# gateway_v1_2A.net
KiCad netlist of a schematic drawn in EAGLE
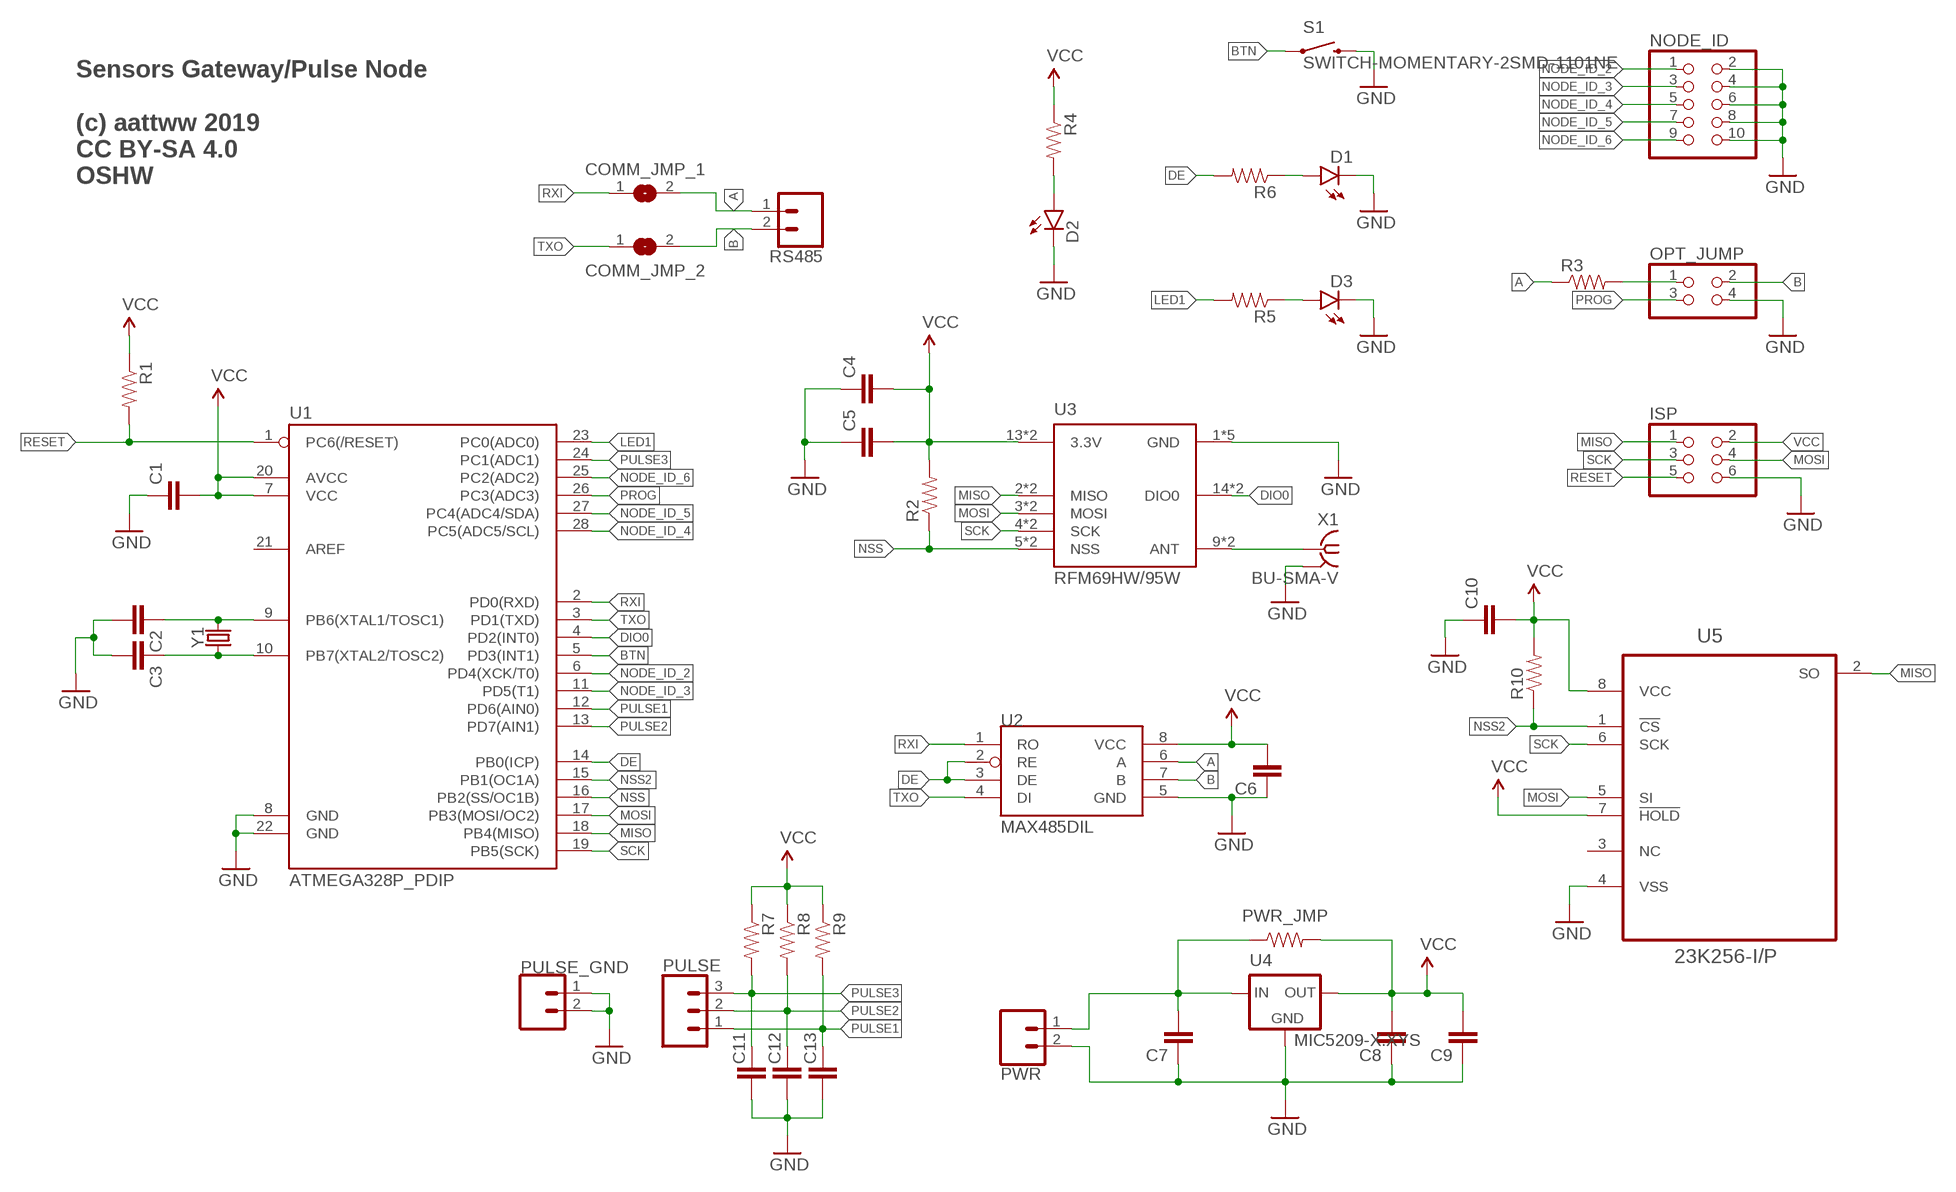
[diagram p0: schematic, sheet 1]

(export (version "E")
  (design (tool "Eeschema 10.0.6"))
  (components
    (comp (ref "C1")
      (value "CAP1206")
      (footprint "eagle-import:1206")
      (libsource (lib "eagle-import") (part "CAP1206"))
    )
    (comp (ref "C2")
      (value "CAP1206")
      (footprint "eagle-import:1206")
      (libsource (lib "eagle-import") (part "CAP1206"))
    )
    (comp (ref "C3")
      (value "CAP1206")
      (footprint "eagle-import:1206")
      (libsource (lib "eagle-import") (part "CAP1206"))
    )
    (comp (ref "C4")
      (value "CAP1206")
      (footprint "eagle-import:1206")
      (libsource (lib "eagle-import") (part "CAP1206"))
    )
    (comp (ref "C5")
      (value "CAP1206")
      (footprint "eagle-import:1206")
      (libsource (lib "eagle-import") (part "CAP1206"))
    )
    (comp (ref "C6")
      (value "CAP1206")
      (footprint "eagle-import:1206")
      (libsource (lib "eagle-import") (part "CAP1206"))
    )
    (comp (ref "C7")
      (value "CAP1206")
      (footprint "eagle-import:1206")
      (libsource (lib "eagle-import") (part "CAP1206"))
    )
    (comp (ref "C8")
      (value "CAP1206")
      (footprint "eagle-import:1206")
      (libsource (lib "eagle-import") (part "CAP1206"))
    )
    (comp (ref "C9")
      (value "CAP1206")
      (footprint "eagle-import:1206")
      (libsource (lib "eagle-import") (part "CAP1206"))
    )
    (comp (ref "C10")
      (value "CAP1206")
      (footprint "eagle-import:1206")
      (libsource (lib "eagle-import") (part "CAP1206"))
    )
    (comp (ref "C11")
      (value "CAP1206")
      (footprint "eagle-import:1206")
      (libsource (lib "eagle-import") (part "CAP1206"))
    )
    (comp (ref "C12")
      (value "CAP1206")
      (footprint "eagle-import:1206")
      (libsource (lib "eagle-import") (part "CAP1206"))
    )
    (comp (ref "C13")
      (value "CAP1206")
      (footprint "eagle-import:1206")
      (libsource (lib "eagle-import") (part "CAP1206"))
    )
    (comp (ref "COMM_JMP_1")
      (value "SJ")
      (footprint "eagle-import:SJ")
      (libsource (lib "eagle-import") (part "SJ"))
    )
    (comp (ref "COMM_JMP_2")
      (value "SJ")
      (footprint "eagle-import:SJ")
      (libsource (lib "eagle-import") (part "SJ"))
    )
    (comp (ref "D1")
      (value "LED1206")
      (footprint "eagle-import:LED-1206")
      (libsource (lib "eagle-import") (part "LED1206"))
    )
    (comp (ref "D2")
      (value "LED1206")
      (footprint "eagle-import:LED-1206")
      (libsource (lib "eagle-import") (part "LED1206"))
    )
    (comp (ref "D3")
      (value "LED1206")
      (footprint "eagle-import:LED-1206")
      (libsource (lib "eagle-import") (part "LED1206"))
    )
    (comp (ref "ISP")
      (value "PINHD-2X3")
      (footprint "eagle-import:2X03")
      (libsource (lib "eagle-import") (part "PINHD-2X3"))
    )
    (comp (ref "NODE_ID")
      (value "PINHD-2X5")
      (footprint "eagle-import:2X05")
      (libsource (lib "eagle-import") (part "PINHD-2X5"))
    )
    (comp (ref "OPT_JUMP")
      (value "PINHD-2X2")
      (footprint "eagle-import:2X02")
      (libsource (lib "eagle-import") (part "PINHD-2X2"))
    )
    (comp (ref "PULSE")
      (value "CONN_03-SCREW-5MM")
      (footprint "eagle-import:SCREWTERMINAL-5MM-3")
      (libsource (lib "eagle-import") (part "CONN_03-SCREW-5MM"))
    )
    (comp (ref "PULSE_GND")
      (value "CONN_025MM")
      (footprint "eagle-import:SCREWTERMINAL-5MM-2")
      (libsource (lib "eagle-import") (part "CONN_025MM"))
    )
    (comp (ref "PWR")
      (value "CONN_025MM")
      (footprint "eagle-import:SCREWTERMINAL-5MM-2")
      (libsource (lib "eagle-import") (part "CONN_025MM"))
    )
    (comp (ref "PWR_JMP")
      (value "RESISTOR1206")
      (footprint "eagle-import:1206")
      (libsource (lib "eagle-import") (part "RESISTOR1206"))
    )
    (comp (ref "R1")
      (value "RESISTOR1206")
      (footprint "eagle-import:1206")
      (libsource (lib "eagle-import") (part "RESISTOR1206"))
    )
    (comp (ref "R2")
      (value "RESISTOR1206")
      (footprint "eagle-import:1206")
      (libsource (lib "eagle-import") (part "RESISTOR1206"))
    )
    (comp (ref "R3")
      (value "RESISTOR1206")
      (footprint "eagle-import:1206")
      (libsource (lib "eagle-import") (part "RESISTOR1206"))
    )
    (comp (ref "R4")
      (value "RESISTOR1206")
      (footprint "eagle-import:1206")
      (libsource (lib "eagle-import") (part "RESISTOR1206"))
    )
    (comp (ref "R5")
      (value "RESISTOR1206")
      (footprint "eagle-import:1206")
      (libsource (lib "eagle-import") (part "RESISTOR1206"))
    )
    (comp (ref "R6")
      (value "RESISTOR1206")
      (footprint "eagle-import:1206")
      (libsource (lib "eagle-import") (part "RESISTOR1206"))
    )
    (comp (ref "R7")
      (value "RESISTOR1206")
      (footprint "eagle-import:1206")
      (libsource (lib "eagle-import") (part "RESISTOR1206"))
    )
    (comp (ref "R8")
      (value "RESISTOR1206")
      (footprint "eagle-import:1206")
      (libsource (lib "eagle-import") (part "RESISTOR1206"))
    )
    (comp (ref "R9")
      (value "RESISTOR1206")
      (footprint "eagle-import:1206")
      (libsource (lib "eagle-import") (part "RESISTOR1206"))
    )
    (comp (ref "R10")
      (value "RESISTOR1206")
      (footprint "eagle-import:1206")
      (libsource (lib "eagle-import") (part "RESISTOR1206"))
    )
    (comp (ref "RS485")
      (value "CONN_025MM")
      (footprint "eagle-import:SCREWTERMINAL-5MM-2")
      (libsource (lib "eagle-import") (part "CONN_025MM"))
    )
    (comp (ref "S1")
      (value "SWITCH-MOMENTARY-2SMD-1101NE")
      (footprint "eagle-import:TACTILE-SWITCH-1101NE")
      (libsource (lib "eagle-import") (part "SWITCH-MOMENTARY-2SMD-1101NE"))
    )
    (comp (ref "U1")
      (value "ATMEGA328P_PDIP")
      (footprint "eagle-import:DIL28-3")
      (libsource (lib "eagle-import") (part "ATMEGA328P_PDIP"))
    )
    (comp (ref "U2")
      (value "MAX485DIL")
      (footprint "eagle-import:DIL08")
      (libsource (lib "eagle-import") (part "MAX485DIL"))
    )
    (comp (ref "U3")
      (value "RFM69HW/95W")
      (footprint "eagle-import:RFM69HW_95W")
      (libsource (lib "eagle-import") (part "RFM69HW/95W"))
    )
    (comp (ref "U4")
      (value "MIC5209-X.XYS")
      (footprint "eagle-import:SOT223")
      (libsource (lib "eagle-import") (part "MIC5209-X.XYS"))
    )
    (comp (ref "U5")
      (value "23K256-I/P")
      (footprint "eagle-import:DIP254P762X533-8")
      (fields (field (name "MPN") "23K256-I/P "))
      (libsource (lib "eagle-import") (part "23K256-I/P"))
    )
    (comp (ref "X1")
      (value "BU-SMA-V")
      (footprint "eagle-import:BU-SMA-V")
      (libsource (lib "eagle-import") (part "BU-SMA-V"))
    )
    (comp (ref "Y1")
      (value "CRYSTALPTH-HC49US")
      (footprint "eagle-import:HC49US")
      (libsource (lib "eagle-import") (part "CRYSTALPTH-HC49US"))
    )
  )
  (nets
    (net (code "1") (name "A") (class "Default")
      (node (ref "COMM_JMP_1") (pin "2") (pinfunction "2_2") (pintype "passive"))
      (node (ref "R3") (pin "1") (pinfunction "1_1") (pintype "passive"))
      (node (ref "RS485") (pin "1") (pinfunction "1_1") (pintype "passive"))
      (node (ref "U2") (pin "6") (pinfunction "A_6") (pintype "bidirectional"))
    )
    (net (code "2") (name "B") (class "Default")
      (node (ref "COMM_JMP_2") (pin "2") (pinfunction "2_2") (pintype "passive"))
      (node (ref "OPT_JUMP") (pin "2") (pinfunction "2_2") (pintype "passive"))
      (node (ref "RS485") (pin "2") (pinfunction "2_2") (pintype "passive"))
      (node (ref "U2") (pin "7") (pinfunction "B_7") (pintype "bidirectional"))
    )
    (net (code "3") (name "BTN") (class "Default")
      (node (ref "S1") (pin "1") (pinfunction "1_1") (pintype "passive"))
      (node (ref "U1") (pin "5") (pinfunction "PD3(INT1)_5") (pintype "bidirectional"))
    )
    (net (code "4") (name "DE") (class "Default")
      (node (ref "R6") (pin "2") (pinfunction "2_2") (pintype "passive"))
      (node (ref "U1") (pin "14") (pinfunction "PB0(ICP)_14") (pintype "bidirectional"))
      (node (ref "U2") (pin "2") (pinfunction "RE_2") (pintype "bidirectional"))
      (node (ref "U2") (pin "3") (pinfunction "DE_3") (pintype "bidirectional"))
    )
    (net (code "5") (name "DIO0") (class "Default")
      (node (ref "U1") (pin "4") (pinfunction "PD2(INT0)_4") (pintype "bidirectional"))
      (node (ref "U3") (pin "14") (pinfunction "DIO0_14") (pintype "bidirectional"))
      (node (ref "U3") (pin "22") (pinfunction "DIO0_22") (pintype "bidirectional"))
    )
    (net (code "6") (name "GND") (class "Default")
      (node (ref "C1") (pin "1") (pinfunction "1_1") (pintype "passive"))
      (node (ref "C10") (pin "1") (pinfunction "1_1") (pintype "passive"))
      (node (ref "C11") (pin "2") (pinfunction "2_2") (pintype "passive"))
      (node (ref "C12") (pin "2") (pinfunction "2_2") (pintype "passive"))
      (node (ref "C13") (pin "2") (pinfunction "2_2") (pintype "passive"))
      (node (ref "C2") (pin "2") (pinfunction "2_2") (pintype "passive"))
      (node (ref "C3") (pin "2") (pinfunction "2_2") (pintype "passive"))
      (node (ref "C4") (pin "1") (pinfunction "1_1") (pintype "passive"))
      (node (ref "C5") (pin "1") (pinfunction "1_1") (pintype "passive"))
      (node (ref "C6") (pin "1") (pinfunction "1_1") (pintype "passive"))
      (node (ref "C7") (pin "1") (pinfunction "1_1") (pintype "passive"))
      (node (ref "C8") (pin "1") (pinfunction "1_1") (pintype "passive"))
      (node (ref "C9") (pin "1") (pinfunction "1_1") (pintype "passive"))
      (node (ref "D1") (pin "C") (pinfunction "C_C") (pintype "passive"))
      (node (ref "D2") (pin "C") (pinfunction "C_C") (pintype "passive"))
      (node (ref "D3") (pin "C") (pinfunction "C_C") (pintype "passive"))
      (node (ref "ISP") (pin "6") (pinfunction "6_6") (pintype "passive"))
      (node (ref "NODE_ID") (pin "10") (pinfunction "10_10") (pintype "passive"))
      (node (ref "NODE_ID") (pin "2") (pinfunction "2_2") (pintype "passive"))
      (node (ref "NODE_ID") (pin "4") (pinfunction "4_4") (pintype "passive"))
      (node (ref "NODE_ID") (pin "6") (pinfunction "6_6") (pintype "passive"))
      (node (ref "NODE_ID") (pin "8") (pinfunction "8_8") (pintype "passive"))
      (node (ref "OPT_JUMP") (pin "4") (pinfunction "4_4") (pintype "passive"))
      (node (ref "PULSE_GND") (pin "1") (pinfunction "1_1") (pintype "passive"))
      (node (ref "PULSE_GND") (pin "2") (pinfunction "2_2") (pintype "passive"))
      (node (ref "PWR") (pin "2") (pinfunction "2_2") (pintype "passive"))
      (node (ref "S1") (pin "2") (pinfunction "2_2") (pintype "passive"))
      (node (ref "U1") (pin "22") (pinfunction "GND_22") (pintype "bidirectional"))
      (node (ref "U1") (pin "8") (pinfunction "GND_8") (pintype "bidirectional"))
      (node (ref "U2") (pin "5") (pinfunction "GND_5") (pintype "bidirectional"))
      (node (ref "U3") (pin "1") (pinfunction "GND_1") (pintype "power_in"))
      (node (ref "U3") (pin "10") (pinfunction "GND_10") (pintype "power_in"))
      (node (ref "U3") (pin "29") (pinfunction "GND_29") (pintype "power_in"))
      (node (ref "U3") (pin "31") (pinfunction "GND_31") (pintype "power_in"))
      (node (ref "U3") (pin "8") (pinfunction "GND_8") (pintype "power_in"))
      (node (ref "U4") (pin "2") (pinfunction "GND_2") (pintype "passive"))
      (node (ref "U4") (pin "4") (pinfunction "GND_4") (pintype "passive"))
      (node (ref "U5") (pin "4") (pinfunction "VSS_4") (pintype "passive"))
      (node (ref "X1") (pin "2") (pinfunction "2_2") (pintype "passive"))
      (node (ref "X1") (pin "3") (pinfunction "2_3") (pintype "passive"))
      (node (ref "X1") (pin "4") (pinfunction "2_4") (pintype "passive"))
      (node (ref "X1") (pin "5") (pinfunction "2_5") (pintype "passive"))
    )
    (net (code "7") (name "LED1") (class "Default")
      (node (ref "R5") (pin "2") (pinfunction "2_2") (pintype "passive"))
      (node (ref "U1") (pin "23") (pinfunction "PC0(ADC0)_23") (pintype "bidirectional"))
    )
    (net (code "8") (name "MISO") (class "Default")
      (node (ref "ISP") (pin "1") (pinfunction "1_1") (pintype "passive"))
      (node (ref "U1") (pin "18") (pinfunction "PB4(MISO)_18") (pintype "bidirectional"))
      (node (ref "U3") (pin "2") (pinfunction "MISO_2") (pintype "bidirectional"))
      (node (ref "U3") (pin "33") (pinfunction "MISO_33") (pintype "bidirectional"))
      (node (ref "U5") (pin "2") (pinfunction "SO_2") (pintype "output"))
    )
    (net (code "9") (name "MOSI") (class "Default")
      (node (ref "ISP") (pin "4") (pinfunction "4_4") (pintype "passive"))
      (node (ref "U1") (pin "17") (pinfunction "PB3(MOSI/OC2)_17") (pintype "bidirectional"))
      (node (ref "U3") (pin "3") (pinfunction "MOSI_3") (pintype "input"))
      (node (ref "U3") (pin "34") (pinfunction "MOSI_34") (pintype "input"))
      (node (ref "U5") (pin "5") (pinfunction "SI_5") (pintype "input"))
    )
    (net (code "10") (name "NODE_ID_2") (class "Default")
      (node (ref "NODE_ID") (pin "1") (pinfunction "1_1") (pintype "passive"))
      (node (ref "U1") (pin "6") (pinfunction "PD4(XCK/T0)_6") (pintype "bidirectional"))
    )
    (net (code "11") (name "NODE_ID_3") (class "Default")
      (node (ref "NODE_ID") (pin "3") (pinfunction "3_3") (pintype "passive"))
      (node (ref "U1") (pin "11") (pinfunction "PD5(T1)_11") (pintype "bidirectional"))
    )
    (net (code "12") (name "NODE_ID_4") (class "Default")
      (node (ref "NODE_ID") (pin "5") (pinfunction "5_5") (pintype "passive"))
      (node (ref "U1") (pin "28") (pinfunction "PC5(ADC5/SCL)_28") (pintype "bidirectional"))
    )
    (net (code "13") (name "NODE_ID_5") (class "Default")
      (node (ref "NODE_ID") (pin "7") (pinfunction "7_7") (pintype "passive"))
      (node (ref "U1") (pin "27") (pinfunction "PC4(ADC4/SDA)_27") (pintype "bidirectional"))
    )
    (net (code "14") (name "NODE_ID_6") (class "Default")
      (node (ref "NODE_ID") (pin "9") (pinfunction "9_9") (pintype "passive"))
      (node (ref "U1") (pin "25") (pinfunction "PC2(ADC2)_25") (pintype "bidirectional"))
    )
    (net (code "15") (name "NSS") (class "Default")
      (node (ref "R2") (pin "1") (pinfunction "1_1") (pintype "passive"))
      (node (ref "U1") (pin "16") (pinfunction "PB2(SS/OC1B)_16") (pintype "bidirectional"))
      (node (ref "U3") (pin "35") (pinfunction "NSS_35") (pintype "input"))
      (node (ref "U3") (pin "5") (pinfunction "NSS_5") (pintype "input"))
    )
    (net (code "16") (name "NSS2") (class "Default")
      (node (ref "R10") (pin "1") (pinfunction "1_1") (pintype "passive"))
      (node (ref "U1") (pin "15") (pinfunction "PB1(OC1A)_15") (pintype "bidirectional"))
      (node (ref "U5") (pin "1") (pinfunction "~{CS}_1") (pintype "input"))
    )
    (net (code "17") (name "Net-(D1-PadA)") (class "Default")
      (node (ref "D1") (pin "A") (pinfunction "A_A") (pintype "passive"))
      (node (ref "R6") (pin "1") (pinfunction "1_1") (pintype "passive"))
    )
    (net (code "18") (name "Net-(D2-PadA)") (class "Default")
      (node (ref "D2") (pin "A") (pinfunction "A_A") (pintype "passive"))
      (node (ref "R4") (pin "2") (pinfunction "2_2") (pintype "passive"))
    )
    (net (code "19") (name "Net-(D3-PadA)") (class "Default")
      (node (ref "D3") (pin "A") (pinfunction "A_A") (pintype "passive"))
      (node (ref "R5") (pin "1") (pinfunction "1_1") (pintype "passive"))
    )
    (net (code "20") (name "Net-(OPT_JUMP-Pad1)") (class "Default")
      (node (ref "OPT_JUMP") (pin "1") (pinfunction "1_1") (pintype "passive"))
      (node (ref "R3") (pin "2") (pinfunction "2_2") (pintype "passive"))
    )
    (net (code "21") (name "Net-(U1-PB6(XTAL1{slash}TOSC1))") (class "Default")
      (node (ref "C2") (pin "1") (pinfunction "1_1") (pintype "passive"))
      (node (ref "U1") (pin "9") (pinfunction "PB6(XTAL1/TOSC1)_9") (pintype "bidirectional"))
      (node (ref "Y1") (pin "2") (pinfunction "2_2") (pintype "passive"))
    )
    (net (code "22") (name "Net-(U1-PB7(XTAL2{slash}TOSC2))") (class "Default")
      (node (ref "C3") (pin "1") (pinfunction "1_1") (pintype "passive"))
      (node (ref "U1") (pin "10") (pinfunction "PB7(XTAL2/TOSC2)_10") (pintype "bidirectional"))
      (node (ref "Y1") (pin "1") (pinfunction "1_1") (pintype "passive"))
    )
    (net (code "23") (name "Net-(U3-ANT-Pad30)") (class "Default")
      (node (ref "U3") (pin "30") (pinfunction "ANT_30") (pintype "passive"))
      (node (ref "U3") (pin "9") (pinfunction "ANT_9") (pintype "passive"))
      (node (ref "X1") (pin "1") (pinfunction "1_1") (pintype "passive"))
    )
    (net (code "24") (name "Net-(U4-IN)") (class "Default")
      (node (ref "C7") (pin "2") (pinfunction "2_2") (pintype "passive"))
      (node (ref "PWR") (pin "1") (pinfunction "1_1") (pintype "passive"))
      (node (ref "PWR_JMP") (pin "1") (pinfunction "1_1") (pintype "passive"))
      (node (ref "U4") (pin "1") (pinfunction "IN_1") (pintype "input"))
    )
    (net (code "25") (name "PROG") (class "Default")
      (node (ref "OPT_JUMP") (pin "3") (pinfunction "3_3") (pintype "passive"))
      (node (ref "U1") (pin "26") (pinfunction "PC3(ADC3)_26") (pintype "bidirectional"))
    )
    (net (code "26") (name "PULSE1") (class "Default")
      (node (ref "C13") (pin "1") (pinfunction "1_1") (pintype "passive"))
      (node (ref "PULSE") (pin "1") (pinfunction "1_1") (pintype "passive"))
      (node (ref "R9") (pin "2") (pinfunction "2_2") (pintype "passive"))
      (node (ref "U1") (pin "12") (pinfunction "PD6(AIN0)_12") (pintype "bidirectional"))
    )
    (net (code "27") (name "PULSE2") (class "Default")
      (node (ref "C12") (pin "1") (pinfunction "1_1") (pintype "passive"))
      (node (ref "PULSE") (pin "2") (pinfunction "2_2") (pintype "passive"))
      (node (ref "R8") (pin "2") (pinfunction "2_2") (pintype "passive"))
      (node (ref "U1") (pin "13") (pinfunction "PD7(AIN1)_13") (pintype "bidirectional"))
    )
    (net (code "28") (name "PULSE3") (class "Default")
      (node (ref "C11") (pin "1") (pinfunction "1_1") (pintype "passive"))
      (node (ref "PULSE") (pin "3") (pinfunction "3_3") (pintype "passive"))
      (node (ref "R7") (pin "2") (pinfunction "2_2") (pintype "passive"))
      (node (ref "U1") (pin "24") (pinfunction "PC1(ADC1)_24") (pintype "bidirectional"))
    )
    (net (code "29") (name "RESET") (class "Default")
      (node (ref "ISP") (pin "5") (pinfunction "5_5") (pintype "passive"))
      (node (ref "R1") (pin "2") (pinfunction "2_2") (pintype "passive"))
      (node (ref "U1") (pin "1") (pinfunction "PC6(/RESET)_1") (pintype "bidirectional"))
    )
    (net (code "30") (name "RXI") (class "Default")
      (node (ref "COMM_JMP_1") (pin "1") (pinfunction "1_1") (pintype "passive"))
      (node (ref "U1") (pin "2") (pinfunction "PD0(RXD)_2") (pintype "bidirectional"))
      (node (ref "U2") (pin "1") (pinfunction "RO_1") (pintype "bidirectional"))
    )
    (net (code "31") (name "SCK") (class "Default")
      (node (ref "ISP") (pin "3") (pinfunction "3_3") (pintype "passive"))
      (node (ref "U1") (pin "19") (pinfunction "PB5(SCK)_19") (pintype "bidirectional"))
      (node (ref "U3") (pin "32") (pinfunction "SCK_32") (pintype "input"))
      (node (ref "U3") (pin "4") (pinfunction "SCK_4") (pintype "input"))
      (node (ref "U5") (pin "6") (pinfunction "SCK_6") (pintype "input"))
    )
    (net (code "32") (name "TXO") (class "Default")
      (node (ref "COMM_JMP_2") (pin "1") (pinfunction "1_1") (pintype "passive"))
      (node (ref "U1") (pin "3") (pinfunction "PD1(TXD)_3") (pintype "bidirectional"))
      (node (ref "U2") (pin "4") (pinfunction "DI_4") (pintype "bidirectional"))
    )
    (net (code "33") (name "VCC") (class "Default")
      (node (ref "C1") (pin "2") (pinfunction "2_2") (pintype "passive"))
      (node (ref "C10") (pin "2") (pinfunction "2_2") (pintype "passive"))
      (node (ref "C4") (pin "2") (pinfunction "2_2") (pintype "passive"))
      (node (ref "C5") (pin "2") (pinfunction "2_2") (pintype "passive"))
      (node (ref "C6") (pin "2") (pinfunction "2_2") (pintype "passive"))
      (node (ref "C8") (pin "2") (pinfunction "2_2") (pintype "passive"))
      (node (ref "C9") (pin "2") (pinfunction "2_2") (pintype "passive"))
      (node (ref "ISP") (pin "2") (pinfunction "2_2") (pintype "passive"))
      (node (ref "PWR_JMP") (pin "2") (pinfunction "2_2") (pintype "passive"))
      (node (ref "R1") (pin "1") (pinfunction "1_1") (pintype "passive"))
      (node (ref "R10") (pin "2") (pinfunction "2_2") (pintype "passive"))
      (node (ref "R2") (pin "2") (pinfunction "2_2") (pintype "passive"))
      (node (ref "R4") (pin "1") (pinfunction "1_1") (pintype "passive"))
      (node (ref "R7") (pin "1") (pinfunction "1_1") (pintype "passive"))
      (node (ref "R8") (pin "1") (pinfunction "1_1") (pintype "passive"))
      (node (ref "R9") (pin "1") (pinfunction "1_1") (pintype "passive"))
      (node (ref "U1") (pin "20") (pinfunction "AVCC_20") (pintype "bidirectional"))
      (node (ref "U1") (pin "7") (pinfunction "VCC_7") (pintype "bidirectional"))
      (node (ref "U2") (pin "8") (pinfunction "VCC_8") (pintype "bidirectional"))
      (node (ref "U3") (pin "13") (pinfunction "3.3V_13") (pintype "power_in"))
      (node (ref "U3") (pin "28") (pinfunction "3.3V_28") (pintype "power_in"))
      (node (ref "U4") (pin "3") (pinfunction "OUT_3") (pintype "passive"))
      (node (ref "U5") (pin "7") (pinfunction "~{HOLD}_7") (pintype "input"))
      (node (ref "U5") (pin "8") (pinfunction "VCC_8") (pintype "power_in"))
    )
    (net (code "34") (name "unconnected-(U1-AREF-Pad21)") (class "Default")
      (node (ref "U1") (pin "21") (pinfunction "AREF_21") (pintype "bidirectional"))
    )
    (net (code "35") (name "unconnected-(U5-NC-Pad3)") (class "Default")
      (node (ref "U5") (pin "3") (pinfunction "NC_3") (pintype "no_connect"))
    )
  )
)
